# WaveGen.net
KiCad netlist of a schematic drawn in Altium Designer
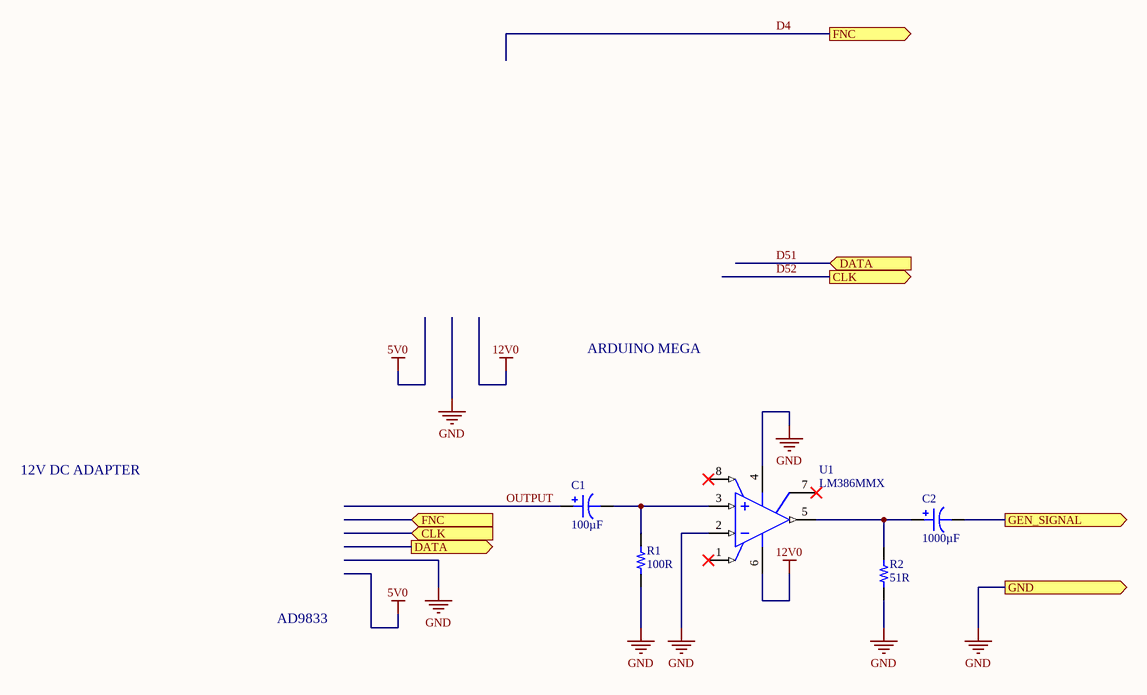
[diagram p0: WaveGen.SchDoc]

(export (version "E")
  (design (tool "Eeschema 10.0.6"))
  (components
    (comp (ref "C1")
      (value "100µF")
      (footprint "CAP TH ALUM ELEC D8.00mm S3.50mm H12.50mm")
      (description "CAP ALUM 150UF 20% 16V RADIAL")
      (fields (field (name "PART NUMBER") "UKL1C151MPD1TD") (field (name "MANUFACTURER") "Nichicon"))
      (libsource (lib "Celestial Altium Library - altium_library") (part "Polarised Capacitor"))
    )
    (comp (ref "C2")
      (value "1000µF")
      (footprint "CAP TH ALUM ELEC D8.00mm S3.50mm H12.50mm")
      (description "CAP ALUM 150UF 20% 16V RADIAL")
      (fields (field (name "PART NUMBER") "UKL1C151MPD1TD") (field (name "MANUFACTURER") "Nichicon"))
      (libsource (lib "Celestial Altium Library - altium_library") (part "Polarised Capacitor"))
    )
    (comp (ref "R1")
      (value "100R")
      (footprint "RES 0805_2012")
      (description "RES 2.7M OHM 0.1% 1/8W 0805")
      (fields (field (name "PART NUMBER") "RG2012P-275-B-T5") (field (name "MANUFACTURER") "Susumu"))
      (libsource (lib "Celestial Altium Library - altium_library") (part "Resistor"))
    )
    (comp (ref "R2")
      (value "51R")
      (footprint "RES 0805_2012")
      (description "RES 2.7M OHM 0.1% 1/8W 0805")
      (fields (field (name "PART NUMBER") "RG2012P-275-B-T5") (field (name "MANUFACTURER") "Susumu"))
      (libsource (lib "Celestial Altium Library - altium_library") (part "Resistor"))
    )
    (comp (ref "U1")
      (value "LM386MMX")
      (footprint "TI-DGK8_L")
      (description "Low Voltage Audio Power Amplifier, 0 to 70 degC, 8-pin SOP (DGK8), Green (RoHS & no Sb/Br)")
      (fields (field (name "PARTNUMBER") "LM386MMX-1/NOPB") (field (name "MANUFACTURER") "Texas Instruments"))
      (libsource (lib "Altium Content Vault") (part "TI-LM386undefined"))
    )
  )
  (nets
    (net (code "4") (name "/GEN_SIGNAL") (class "Default")
      (node (ref "C2") (pin "2") (pinfunction "2_2") (pintype "passive"))
    )
    (net (code "5") (name "/OUTPUT") (class "Default")
      (node (ref "C1") (pin "1") (pinfunction "1_1") (pintype "passive"))
    )
    (net (code "7") (name "12V0") (class "Default")
      (node (ref "U1") (pin "6") (pinfunction "VS_6") (pintype "power_in"))
    )
    (net (code "8") (name "GND") (class "Default")
      (node (ref "R1") (pin "1") (pinfunction "1_1") (pintype "passive"))
      (node (ref "R2") (pin "1") (pinfunction "1_1") (pintype "passive"))
      (node (ref "U1") (pin "2") (pinfunction "IN-_2") (pintype "input"))
      (node (ref "U1") (pin "4") (pinfunction "GND_4") (pintype "power_in"))
    )
    (net (code "9") (name "Net-(U1-IN+)") (class "Default")
      (node (ref "C1") (pin "2") (pinfunction "2_2") (pintype "passive"))
      (node (ref "R1") (pin "2") (pinfunction "2_2") (pintype "passive"))
      (node (ref "U1") (pin "3") (pinfunction "IN+_3") (pintype "input"))
    )
    (net (code "10") (name "Net-(U1-VOUT)") (class "Default")
      (node (ref "C2") (pin "1") (pinfunction "1_1") (pintype "passive"))
      (node (ref "R2") (pin "2") (pinfunction "2_2") (pintype "passive"))
      (node (ref "U1") (pin "5") (pinfunction "VOUT_5") (pintype "output"))
    )
    (net (code "11") (name "unconnected-(U1-BYPASS-Pad7)") (class "Default")
      (node (ref "U1") (pin "7") (pinfunction "BYPASS_7") (pintype "passive+no_connect"))
    )
    (net (code "12") (name "unconnected-(U1-GAIN-Pad1)") (class "Default")
      (node (ref "U1") (pin "1") (pinfunction "GAIN_1") (pintype "input+no_connect"))
    )
    (net (code "13") (name "unconnected-(U1-GAIN-Pad8)") (class "Default")
      (node (ref "U1") (pin "8") (pinfunction "GAIN_8") (pintype "input+no_connect"))
    )
  )
)
